# schemat_eagle.net
KiCad netlist of a schematic drawn in EAGLE
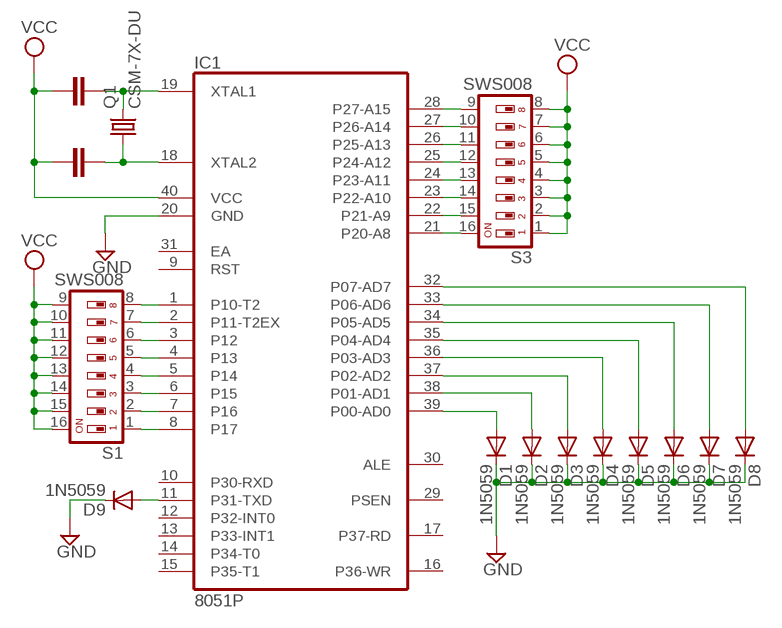
[diagram p0: schematic, sheet 1]

(export (version "E")
  (design (tool "Eeschema 10.0.6"))
  (components
    (comp (ref "D1")
      (value "1N5059")
      (footprint "eagle-import:DO204-10")
      (libsource (lib "eagle-import") (part "1N5059"))
    )
    (comp (ref "D2")
      (value "1N5059")
      (footprint "eagle-import:DO204-10")
      (libsource (lib "eagle-import") (part "1N5059"))
    )
    (comp (ref "D3")
      (value "1N5059")
      (footprint "eagle-import:DO204-10")
      (libsource (lib "eagle-import") (part "1N5059"))
    )
    (comp (ref "D4")
      (value "1N5059")
      (footprint "eagle-import:DO204-10")
      (libsource (lib "eagle-import") (part "1N5059"))
    )
    (comp (ref "D5")
      (value "1N5059")
      (footprint "eagle-import:DO204-10")
      (libsource (lib "eagle-import") (part "1N5059"))
    )
    (comp (ref "D6")
      (value "1N5059")
      (footprint "eagle-import:DO204-10")
      (libsource (lib "eagle-import") (part "1N5059"))
    )
    (comp (ref "D7")
      (value "1N5059")
      (footprint "eagle-import:DO204-10")
      (libsource (lib "eagle-import") (part "1N5059"))
    )
    (comp (ref "D8")
      (value "1N5059")
      (footprint "eagle-import:DO204-10")
      (libsource (lib "eagle-import") (part "1N5059"))
    )
    (comp (ref "D9")
      (value "1N5059")
      (footprint "eagle-import:DO204-10")
      (libsource (lib "eagle-import") (part "1N5059"))
    )
    (comp (ref "IC1")
      (value "8051P")
      (footprint "eagle-import:DIL40")
      (libsource (lib "eagle-import") (part "8051P"))
    )
    (comp (ref "Q1")
      (value "CSM-7X-DU")
      (footprint "eagle-import:CSM-7X-DU")
      (libsource (lib "eagle-import") (part "CSM-7X-DU"))
    )
    (comp (ref "S1")
      (value "SWS008")
      (footprint "eagle-import:SMS-008")
      (libsource (lib "eagle-import") (part "SWS008"))
    )
    (comp (ref "S3")
      (value "SWS008")
      (footprint "eagle-import:SMS-008")
      (libsource (lib "eagle-import") (part "SWS008"))
    )
  )
  (nets
    (net (code "1") (name "GND") (class "Default")
      (node (ref "D1") (pin "C") (pinfunction "C_C") (pintype "passive"))
      (node (ref "D2") (pin "C") (pinfunction "C_C") (pintype "passive"))
      (node (ref "D3") (pin "C") (pinfunction "C_C") (pintype "passive"))
      (node (ref "D4") (pin "C") (pinfunction "C_C") (pintype "passive"))
      (node (ref "D5") (pin "C") (pinfunction "C_C") (pintype "passive"))
      (node (ref "D6") (pin "C") (pinfunction "C_C") (pintype "passive"))
      (node (ref "D7") (pin "C") (pinfunction "C_C") (pintype "passive"))
      (node (ref "D8") (pin "C") (pinfunction "C_C") (pintype "passive"))
      (node (ref "D9") (pin "C") (pinfunction "C_C") (pintype "passive"))
      (node (ref "IC1") (pin "20") (pinfunction "GND_20") (pintype "power_in"))
    )
    (net (code "2") (name "Net-(IC1-P00-AD0)") (class "Default")
      (node (ref "D1") (pin "A") (pinfunction "A_A") (pintype "passive"))
      (node (ref "IC1") (pin "39") (pinfunction "P00-AD0_39") (pintype "bidirectional"))
    )
    (net (code "3") (name "Net-(IC1-P01-AD1)") (class "Default")
      (node (ref "D2") (pin "A") (pinfunction "A_A") (pintype "passive"))
      (node (ref "IC1") (pin "38") (pinfunction "P01-AD1_38") (pintype "bidirectional"))
    )
    (net (code "4") (name "Net-(IC1-P02-AD2)") (class "Default")
      (node (ref "D3") (pin "A") (pinfunction "A_A") (pintype "passive"))
      (node (ref "IC1") (pin "37") (pinfunction "P02-AD2_37") (pintype "bidirectional"))
    )
    (net (code "5") (name "Net-(IC1-P03-AD3)") (class "Default")
      (node (ref "D4") (pin "A") (pinfunction "A_A") (pintype "passive"))
      (node (ref "IC1") (pin "36") (pinfunction "P03-AD3_36") (pintype "bidirectional"))
    )
    (net (code "6") (name "Net-(IC1-P04-AD4)") (class "Default")
      (node (ref "D5") (pin "A") (pinfunction "A_A") (pintype "passive"))
      (node (ref "IC1") (pin "35") (pinfunction "P04-AD4_35") (pintype "bidirectional"))
    )
    (net (code "7") (name "Net-(IC1-P05-AD5)") (class "Default")
      (node (ref "D6") (pin "A") (pinfunction "A_A") (pintype "passive"))
      (node (ref "IC1") (pin "34") (pinfunction "P05-AD5_34") (pintype "bidirectional"))
    )
    (net (code "8") (name "Net-(IC1-P06-AD6)") (class "Default")
      (node (ref "D7") (pin "A") (pinfunction "A_A") (pintype "passive"))
      (node (ref "IC1") (pin "33") (pinfunction "P06-AD6_33") (pintype "bidirectional"))
    )
    (net (code "9") (name "Net-(IC1-P07-AD7)") (class "Default")
      (node (ref "D8") (pin "A") (pinfunction "A_A") (pintype "passive"))
      (node (ref "IC1") (pin "32") (pinfunction "P07-AD7_32") (pintype "bidirectional"))
    )
    (net (code "10") (name "Net-(IC1-P10-T2)") (class "Default")
      (node (ref "IC1") (pin "1") (pinfunction "P10-T2_1") (pintype "bidirectional"))
      (node (ref "S1") (pin "8") (pinfunction "8_8") (pintype "passive"))
    )
    (net (code "11") (name "Net-(IC1-P11-T2EX)") (class "Default")
      (node (ref "IC1") (pin "2") (pinfunction "P11-T2EX_2") (pintype "bidirectional"))
      (node (ref "S1") (pin "7") (pinfunction "7_7") (pintype "passive"))
    )
    (net (code "12") (name "Net-(IC1-P12)") (class "Default")
      (node (ref "IC1") (pin "3") (pinfunction "P12_3") (pintype "bidirectional"))
      (node (ref "S1") (pin "6") (pinfunction "6_6") (pintype "passive"))
    )
    (net (code "13") (name "Net-(IC1-P13)") (class "Default")
      (node (ref "IC1") (pin "4") (pinfunction "P13_4") (pintype "bidirectional"))
      (node (ref "S1") (pin "5") (pinfunction "5_5") (pintype "passive"))
    )
    (net (code "14") (name "Net-(IC1-P14)") (class "Default")
      (node (ref "IC1") (pin "5") (pinfunction "P14_5") (pintype "bidirectional"))
      (node (ref "S1") (pin "4") (pinfunction "4_4") (pintype "passive"))
    )
    (net (code "15") (name "Net-(IC1-P15)") (class "Default")
      (node (ref "IC1") (pin "6") (pinfunction "P15_6") (pintype "bidirectional"))
      (node (ref "S1") (pin "3") (pinfunction "3_3") (pintype "passive"))
    )
    (net (code "16") (name "Net-(IC1-P16)") (class "Default")
      (node (ref "IC1") (pin "7") (pinfunction "P16_7") (pintype "bidirectional"))
      (node (ref "S1") (pin "2") (pinfunction "2_2") (pintype "passive"))
    )
    (net (code "17") (name "Net-(IC1-P17)") (class "Default")
      (node (ref "IC1") (pin "8") (pinfunction "P17_8") (pintype "bidirectional"))
      (node (ref "S1") (pin "1") (pinfunction "1_1") (pintype "passive"))
    )
    (net (code "18") (name "Net-(IC1-P20-A8)") (class "Default")
      (node (ref "IC1") (pin "21") (pinfunction "P20-A8_21") (pintype "bidirectional"))
      (node (ref "S3") (pin "16") (pinfunction "16_16") (pintype "passive"))
    )
    (net (code "19") (name "Net-(IC1-P21-A9)") (class "Default")
      (node (ref "IC1") (pin "22") (pinfunction "P21-A9_22") (pintype "bidirectional"))
      (node (ref "S3") (pin "15") (pinfunction "15_15") (pintype "passive"))
    )
    (net (code "20") (name "Net-(IC1-P22-A10)") (class "Default")
      (node (ref "IC1") (pin "23") (pinfunction "P22-A10_23") (pintype "bidirectional"))
      (node (ref "S3") (pin "14") (pinfunction "14_14") (pintype "passive"))
    )
    (net (code "21") (name "Net-(IC1-P23-A11)") (class "Default")
      (node (ref "IC1") (pin "24") (pinfunction "P23-A11_24") (pintype "bidirectional"))
      (node (ref "S3") (pin "13") (pinfunction "13_13") (pintype "passive"))
    )
    (net (code "22") (name "Net-(IC1-P24-A12)") (class "Default")
      (node (ref "IC1") (pin "25") (pinfunction "P24-A12_25") (pintype "bidirectional"))
      (node (ref "S3") (pin "12") (pinfunction "12_12") (pintype "passive"))
    )
    (net (code "23") (name "Net-(IC1-P25-A13)") (class "Default")
      (node (ref "IC1") (pin "26") (pinfunction "P25-A13_26") (pintype "bidirectional"))
      (node (ref "S3") (pin "11") (pinfunction "11_11") (pintype "passive"))
    )
    (net (code "24") (name "Net-(IC1-P26-A14)") (class "Default")
      (node (ref "IC1") (pin "27") (pinfunction "P26-A14_27") (pintype "bidirectional"))
      (node (ref "S3") (pin "10") (pinfunction "10_10") (pintype "passive"))
    )
    (net (code "25") (name "Net-(IC1-P27-A15)") (class "Default")
      (node (ref "IC1") (pin "28") (pinfunction "P27-A15_28") (pintype "bidirectional"))
      (node (ref "S3") (pin "9") (pinfunction "9_9") (pintype "passive"))
    )
    (net (code "26") (name "Net-(IC1-P31-TXD)") (class "Default")
      (node (ref "D9") (pin "A") (pinfunction "A_A") (pintype "passive"))
      (node (ref "IC1") (pin "11") (pinfunction "P31-TXD_11") (pintype "bidirectional"))
    )
    (net (code "27") (name "Net-(IC1-XTAL1)") (class "Default")
      (node (ref "IC1") (pin "19") (pinfunction "XTAL1_19") (pintype "input"))
      (node (ref "Q1") (pin "2") (pinfunction "2_2") (pintype "passive"))
    )
    (net (code "28") (name "Net-(IC1-XTAL2)") (class "Default")
      (node (ref "IC1") (pin "18") (pinfunction "XTAL2_18") (pintype "input"))
      (node (ref "Q1") (pin "1") (pinfunction "1_1") (pintype "passive"))
    )
    (net (code "29") (name "VCC") (class "Default")
      (node (ref "IC1") (pin "40") (pinfunction "VCC_40") (pintype "power_in"))
      (node (ref "S1") (pin "10") (pinfunction "10_10") (pintype "passive"))
      (node (ref "S1") (pin "11") (pinfunction "11_11") (pintype "passive"))
      (node (ref "S1") (pin "12") (pinfunction "12_12") (pintype "passive"))
      (node (ref "S1") (pin "13") (pinfunction "13_13") (pintype "passive"))
      (node (ref "S1") (pin "14") (pinfunction "14_14") (pintype "passive"))
      (node (ref "S1") (pin "15") (pinfunction "15_15") (pintype "passive"))
      (node (ref "S1") (pin "16") (pinfunction "16_16") (pintype "passive"))
      (node (ref "S1") (pin "9") (pinfunction "9_9") (pintype "passive"))
      (node (ref "S3") (pin "1") (pinfunction "1_1") (pintype "passive"))
      (node (ref "S3") (pin "2") (pinfunction "2_2") (pintype "passive"))
      (node (ref "S3") (pin "3") (pinfunction "3_3") (pintype "passive"))
      (node (ref "S3") (pin "4") (pinfunction "4_4") (pintype "passive"))
      (node (ref "S3") (pin "5") (pinfunction "5_5") (pintype "passive"))
      (node (ref "S3") (pin "6") (pinfunction "6_6") (pintype "passive"))
      (node (ref "S3") (pin "7") (pinfunction "7_7") (pintype "passive"))
      (node (ref "S3") (pin "8") (pinfunction "8_8") (pintype "passive"))
    )
    (net (code "30") (name "unconnected-(IC1-ALE-Pad30)") (class "Default")
      (node (ref "IC1") (pin "30") (pinfunction "ALE_30") (pintype "output"))
    )
    (net (code "31") (name "unconnected-(IC1-EA-Pad31)") (class "Default")
      (node (ref "IC1") (pin "31") (pinfunction "EA_31") (pintype "input"))
    )
    (net (code "32") (name "unconnected-(IC1-P30-RXD-Pad10)") (class "Default")
      (node (ref "IC1") (pin "10") (pinfunction "P30-RXD_10") (pintype "bidirectional"))
    )
    (net (code "33") (name "unconnected-(IC1-P32-INT0-Pad12)") (class "Default")
      (node (ref "IC1") (pin "12") (pinfunction "P32-INT0_12") (pintype "bidirectional"))
    )
    (net (code "34") (name "unconnected-(IC1-P33-INT1-Pad13)") (class "Default")
      (node (ref "IC1") (pin "13") (pinfunction "P33-INT1_13") (pintype "bidirectional"))
    )
    (net (code "35") (name "unconnected-(IC1-P34-T0-Pad14)") (class "Default")
      (node (ref "IC1") (pin "14") (pinfunction "P34-T0_14") (pintype "bidirectional"))
    )
    (net (code "36") (name "unconnected-(IC1-P35-T1-Pad15)") (class "Default")
      (node (ref "IC1") (pin "15") (pinfunction "P35-T1_15") (pintype "bidirectional"))
    )
    (net (code "37") (name "unconnected-(IC1-P36-WR-Pad16)") (class "Default")
      (node (ref "IC1") (pin "16") (pinfunction "P36-WR_16") (pintype "bidirectional"))
    )
    (net (code "38") (name "unconnected-(IC1-P37-RD-Pad17)") (class "Default")
      (node (ref "IC1") (pin "17") (pinfunction "P37-RD_17") (pintype "bidirectional"))
    )
    (net (code "39") (name "unconnected-(IC1-PSEN-Pad29)") (class "Default")
      (node (ref "IC1") (pin "29") (pinfunction "PSEN_29") (pintype "output"))
    )
    (net (code "40") (name "unconnected-(IC1-RST-Pad9)") (class "Default")
      (node (ref "IC1") (pin "9") (pinfunction "RST_9") (pintype "input"))
    )
  )
)
